# mic_v4.net
KiCad netlist of a schematic drawn in EAGLE
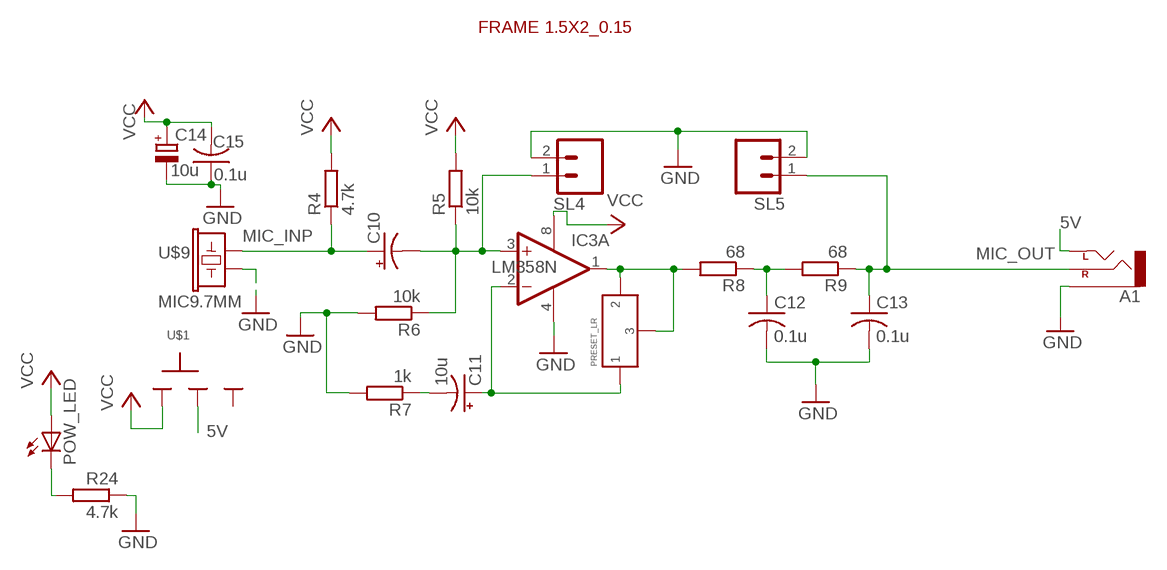
[diagram p0: schematic, sheet 1]

(export (version "E")
  (design (tool "Eeschema 10.0.6"))
  (components
    (comp (ref "A1")
      (value "AUX-CONNECTOR_CEDT_JANUARY_2015_V5_AUDIO-JACKPTH")
      (footprint "eagle-import:AUX-CONNECTOR_CEDT_JANUARY_2015_V5_AUDIO-JACK")
      (libsource (lib "eagle-import") (part "AUX-CONNECTOR_CEDT_JANUARY_2015_V5_AUDIO-JACKPTH"))
    )
    (comp (ref "C10")
      (value "CPOL-USE2.5-5")
      (footprint "eagle-import:E2,5-5")
      (libsource (lib "eagle-import") (part "CPOL-USE2.5-5"))
    )
    (comp (ref "C11")
      (value "10u")
      (footprint "eagle-import:E2,5-5")
      (libsource (lib "eagle-import") (part "CPOL-USE2.5-5"))
    )
    (comp (ref "C12")
      (value "0.1u")
      (footprint "eagle-import:C025-024X044")
      (libsource (lib "eagle-import") (part "C-US025-024X044"))
    )
    (comp (ref "C13")
      (value "0.1u")
      (footprint "eagle-import:C025-024X044")
      (libsource (lib "eagle-import") (part "C-US025-024X044"))
    )
    (comp (ref "C14")
      (value "10u")
      (footprint "eagle-import:E2,5-5")
      (libsource (lib "eagle-import") (part "CPOL-EUE2.5-5"))
    )
    (comp (ref "C15")
      (value "0.1u")
      (footprint "eagle-import:C025-024X044")
      (libsource (lib "eagle-import") (part "C-US025-024X044"))
    )
    (comp (ref "IC3")
      (value "LM358N")
      (footprint "eagle-import:DIL08")
      (libsource (lib "eagle-import") (part "LM358N"))
    )
    (comp (ref "POW_LED")
      (value "LED3MM")
      (footprint "eagle-import:LED3MM")
      (libsource (lib "eagle-import") (part "LED3MM"))
    )
    (comp (ref "R4")
      (value "4.7k")
      (footprint "eagle-import:0204_7")
      (libsource (lib "eagle-import") (part "R-EU_0204/7"))
    )
    (comp (ref "R5")
      (value "10k")
      (footprint "eagle-import:0204_7")
      (libsource (lib "eagle-import") (part "R-EU_0204/7"))
    )
    (comp (ref "R6")
      (value "10k")
      (footprint "eagle-import:0204_7")
      (libsource (lib "eagle-import") (part "R-EU_0204/7"))
    )
    (comp (ref "R7")
      (value "1k")
      (footprint "eagle-import:0204_7")
      (libsource (lib "eagle-import") (part "R-EU_0204/7"))
    )
    (comp (ref "R8")
      (value "68")
      (footprint "eagle-import:0204_7")
      (libsource (lib "eagle-import") (part "R-EU_0204/7"))
    )
    (comp (ref "R9")
      (value "68")
      (footprint "eagle-import:0204_7")
      (libsource (lib "eagle-import") (part "R-EU_0204/7"))
    )
    (comp (ref "R24")
      (value "4.7k")
      (footprint "eagle-import:0204_7")
      (libsource (lib "eagle-import") (part "R-EU_0204/7"))
    )
    (comp (ref "SL4")
      (value "M02")
      (footprint "eagle-import:02P")
      (libsource (lib "eagle-import") (part "M02"))
    )
    (comp (ref "SL5")
      (value "M02")
      (footprint "eagle-import:02P")
      (libsource (lib "eagle-import") (part "M02"))
    )
    (comp (ref "U$1")
      (value "SLIDESWITCH-BIG")
      (footprint "eagle-import:BIGSWITCH")
      (libsource (lib "eagle-import") (part "SLIDESWITCH-BIG"))
    )
    (comp (ref "U$2")
      (value "FRAME_1.5X2_RAD_0.15")
      (footprint "eagle-import:FRAME_1.5X2_RAD_0.15")
      (libsource (lib "eagle-import") (part "FRAME_1.5X2_RAD_0.15"))
    )
    (comp (ref "U$6")
      (value "PRESET_LR")
      (footprint "eagle-import:PRESET_LR")
      (libsource (lib "eagle-import") (part "PRESET_LR"))
    )
    (comp (ref "U$9")
      (value "MIC9.7MM")
      (footprint "eagle-import:MIC-9.7MM")
      (libsource (lib "eagle-import") (part "MIC9.7MM"))
    )
  )
  (nets
    (net (code "1") (name "/5V") (class "Default")
      (node (ref "A1") (pin "TIP") (pinfunction "LEFT_TIP") (pintype "bidirectional"))
      (node (ref "U$1") (pin "2") (pinfunction "2_2") (pintype "bidirectional"))
    )
    (net (code "2") (name "/MIC_INP") (class "Default")
      (node (ref "C10") (pin "+") (pinfunction "+_+") (pintype "passive"))
      (node (ref "R4") (pin "1") (pinfunction "1_1") (pintype "passive"))
      (node (ref "U$9") (pin "1") (pinfunction "1_1") (pintype "passive"))
    )
    (net (code "3") (name "/MIC_OUT") (class "Default")
      (node (ref "A1") (pin "RING") (pinfunction "RIGHT_RING") (pintype "bidirectional"))
      (node (ref "C13") (pin "1") (pinfunction "1_1") (pintype "passive"))
      (node (ref "R9") (pin "1") (pinfunction "1_1") (pintype "passive"))
      (node (ref "SL5") (pin "1") (pinfunction "1_1") (pintype "passive"))
    )
    (net (code "4") (name "GND") (class "Default")
      (node (ref "A1") (pin "SLEEVE") (pinfunction "SLEEVE_SLEEVE") (pintype "bidirectional"))
      (node (ref "C12") (pin "2") (pinfunction "2_2") (pintype "passive"))
      (node (ref "C13") (pin "2") (pinfunction "2_2") (pintype "passive"))
      (node (ref "C14") (pin "-") (pinfunction "-_-") (pintype "passive"))
      (node (ref "C15") (pin "1") (pinfunction "1_1") (pintype "passive"))
      (node (ref "IC3") (pin "4") (pinfunction "V-_4") (pintype "power_in"))
      (node (ref "R24") (pin "1") (pinfunction "1_1") (pintype "passive"))
      (node (ref "R6") (pin "2") (pinfunction "2_2") (pintype "passive"))
      (node (ref "R7") (pin "2") (pinfunction "2_2") (pintype "passive"))
      (node (ref "SL4") (pin "2") (pinfunction "2_2") (pintype "passive"))
      (node (ref "SL5") (pin "2") (pinfunction "2_2") (pintype "passive"))
      (node (ref "U$9") (pin "2") (pinfunction "2_2") (pintype "passive"))
    )
    (net (code "5") (name "Net-(C11-Pad-)") (class "Default")
      (node (ref "C11") (pin "-") (pinfunction "-_-") (pintype "passive"))
      (node (ref "R7") (pin "1") (pinfunction "1_1") (pintype "passive"))
    )
    (net (code "6") (name "Net-(C12-Pad1)") (class "Default")
      (node (ref "C12") (pin "1") (pinfunction "1_1") (pintype "passive"))
      (node (ref "R8") (pin "1") (pinfunction "1_1") (pintype "passive"))
      (node (ref "R9") (pin "2") (pinfunction "2_2") (pintype "passive"))
    )
    (net (code "7") (name "Net-(IC3A-+IN)") (class "Default")
      (node (ref "C10") (pin "-") (pinfunction "-_-") (pintype "passive"))
      (node (ref "IC3") (pin "3") (pinfunction "+IN_3") (pintype "input"))
      (node (ref "R5") (pin "1") (pinfunction "1_1") (pintype "passive"))
      (node (ref "R6") (pin "1") (pinfunction "1_1") (pintype "passive"))
      (node (ref "SL4") (pin "1") (pinfunction "1_1") (pintype "passive"))
    )
    (net (code "8") (name "Net-(IC3A--IN)") (class "Default")
      (node (ref "C11") (pin "+") (pinfunction "+_+") (pintype "passive"))
      (node (ref "IC3") (pin "2") (pinfunction "-IN_2") (pintype "input"))
      (node (ref "U$6") (pin "P$1") (pinfunction "1_P$1") (pintype "passive"))
    )
    (net (code "9") (name "Net-(IC3A-OUT)") (class "Default")
      (node (ref "IC3") (pin "1") (pinfunction "OUT_1") (pintype "output"))
      (node (ref "R8") (pin "2") (pinfunction "2_2") (pintype "passive"))
      (node (ref "U$6") (pin "P$2") (pinfunction "2_P$2") (pintype "passive"))
      (node (ref "U$6") (pin "P$3") (pinfunction "3_P$3") (pintype "passive"))
    )
    (net (code "10") (name "Net-(POW_LED-C)") (class "Default")
      (node (ref "POW_LED") (pin "K") (pinfunction "C_K") (pintype "passive"))
      (node (ref "R24") (pin "2") (pinfunction "2_2") (pintype "passive"))
    )
    (net (code "11") (name "VCC") (class "Default")
      (node (ref "C14") (pin "+") (pinfunction "+_+") (pintype "passive"))
      (node (ref "C15") (pin "2") (pinfunction "2_2") (pintype "passive"))
      (node (ref "IC3") (pin "8") (pinfunction "V+_8") (pintype "power_in"))
      (node (ref "POW_LED") (pin "A") (pinfunction "A_A") (pintype "passive"))
      (node (ref "R4") (pin "2") (pinfunction "2_2") (pintype "passive"))
      (node (ref "R5") (pin "2") (pinfunction "2_2") (pintype "passive"))
      (node (ref "U$1") (pin "1") (pinfunction "1_1") (pintype "bidirectional"))
    )
    (net (code "12") (name "unconnected-(U$1-Pad3)") (class "Default")
      (node (ref "U$1") (pin "3") (pinfunction "3_3") (pintype "bidirectional"))
    )
  )
)
